# marlin_interface.net
KiCad netlist of a schematic drawn in EAGLE
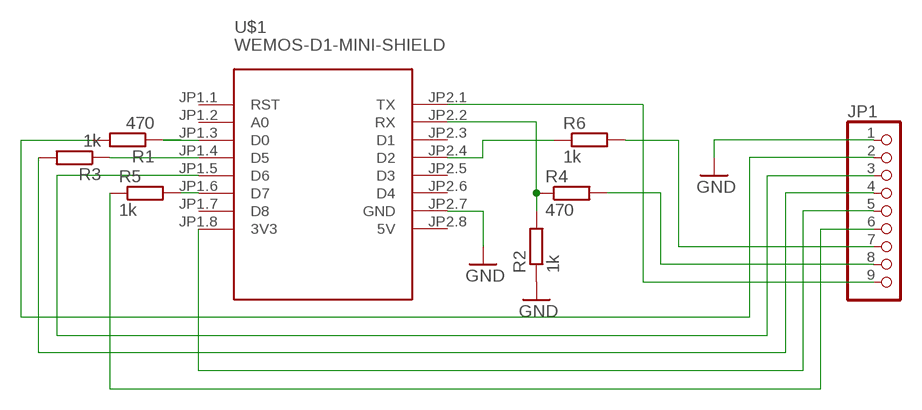
[diagram p0: schematic, sheet 1]

(export (version "E")
  (design (tool "Eeschema 10.0.6"))
  (components
    (comp (ref "JP1")
      (value "PINHD-1X9/90")
      (footprint "eagle-import:1X09_90")
      (libsource (lib "eagle-import") (part "PINHD-1X9/90"))
    )
    (comp (ref "R1")
      (value "470")
      (footprint "eagle-import:0204_5")
      (libsource (lib "eagle-import") (part "R-EU_0204/5"))
    )
    (comp (ref "R2")
      (value "1k")
      (footprint "eagle-import:0204_5")
      (libsource (lib "eagle-import") (part "R-EU_0204/5"))
    )
    (comp (ref "R3")
      (value "1k")
      (footprint "eagle-import:0204_5")
      (libsource (lib "eagle-import") (part "R-EU_0204/5"))
    )
    (comp (ref "R4")
      (value "470")
      (footprint "eagle-import:0204_5")
      (libsource (lib "eagle-import") (part "R-EU_0204/5"))
    )
    (comp (ref "R5")
      (value "1k")
      (footprint "eagle-import:0204_5")
      (libsource (lib "eagle-import") (part "R-EU_0204/5"))
    )
    (comp (ref "R6")
      (value "1k")
      (footprint "eagle-import:0204_5")
      (libsource (lib "eagle-import") (part "R-EU_0204/5"))
    )
    (comp (ref "U$1")
      (value "WEMOS-D1-MINI-SHIELD")
      (footprint "eagle-import:WEMOS-D1-MINI-SHIELD")
      (libsource (lib "eagle-import") (part "WEMOS-D1-MINI-SHIELD"))
    )
  )
  (nets
    (net (code "1") (name "/5V") (class "Default")
      (node (ref "U$1") (pin "JP2.8") (pinfunction "5V_JP2.8") (pintype "power_in"))
    )
    (net (code "2") (name "GND") (class "Default")
      (node (ref "JP1") (pin "1") (pinfunction "1_1") (pintype "passive"))
      (node (ref "R2") (pin "1") (pinfunction "1_1") (pintype "passive"))
      (node (ref "U$1") (pin "JP2.7") (pinfunction "GND_JP2.7") (pintype "power_in"))
    )
    (net (code "3") (name "Net-(JP1-Pad2)") (class "Default")
      (node (ref "JP1") (pin "2") (pinfunction "2_2") (pintype "passive"))
      (node (ref "R1") (pin "2") (pinfunction "2_2") (pintype "passive"))
    )
    (net (code "4") (name "Net-(JP1-Pad4)") (class "Default")
      (node (ref "JP1") (pin "4") (pinfunction "4_4") (pintype "passive"))
      (node (ref "R3") (pin "2") (pinfunction "2_2") (pintype "passive"))
    )
    (net (code "5") (name "Net-(JP1-Pad6)") (class "Default")
      (node (ref "JP1") (pin "6") (pinfunction "6_6") (pintype "passive"))
      (node (ref "R5") (pin "1") (pinfunction "1_1") (pintype "passive"))
    )
    (net (code "6") (name "Net-(JP1-Pad7)") (class "Default")
      (node (ref "JP1") (pin "7") (pinfunction "7_7") (pintype "passive"))
      (node (ref "R6") (pin "2") (pinfunction "2_2") (pintype "passive"))
    )
    (net (code "7") (name "Net-(JP1-Pad8)") (class "Default")
      (node (ref "JP1") (pin "8") (pinfunction "8_8") (pintype "passive"))
      (node (ref "R4") (pin "2") (pinfunction "2_2") (pintype "passive"))
    )
    (net (code "8") (name "Net-(U$1-3V3)") (class "Default")
      (node (ref "JP1") (pin "5") (pinfunction "5_5") (pintype "passive"))
      (node (ref "U$1") (pin "JP1.8") (pinfunction "3V3_JP1.8") (pintype "power_in"))
    )
    (net (code "9") (name "Net-(U$1-D0)") (class "Default")
      (node (ref "R1") (pin "1") (pinfunction "1_1") (pintype "passive"))
      (node (ref "U$1") (pin "JP1.3") (pinfunction "D0_JP1.3") (pintype "bidirectional"))
    )
    (net (code "10") (name "Net-(U$1-D2)") (class "Default")
      (node (ref "R6") (pin "1") (pinfunction "1_1") (pintype "passive"))
      (node (ref "U$1") (pin "JP2.4") (pinfunction "D2_JP2.4") (pintype "bidirectional"))
    )
    (net (code "11") (name "Net-(U$1-D5)") (class "Default")
      (node (ref "R3") (pin "1") (pinfunction "1_1") (pintype "passive"))
      (node (ref "U$1") (pin "JP1.4") (pinfunction "D5_JP1.4") (pintype "bidirectional"))
    )
    (net (code "12") (name "Net-(U$1-D6)") (class "Default")
      (node (ref "JP1") (pin "3") (pinfunction "3_3") (pintype "passive"))
      (node (ref "U$1") (pin "JP1.5") (pinfunction "D6_JP1.5") (pintype "bidirectional"))
    )
    (net (code "13") (name "Net-(U$1-D7)") (class "Default")
      (node (ref "R5") (pin "2") (pinfunction "2_2") (pintype "passive"))
      (node (ref "U$1") (pin "JP1.6") (pinfunction "D7_JP1.6") (pintype "bidirectional"))
    )
    (net (code "14") (name "Net-(U$1-RX)") (class "Default")
      (node (ref "R2") (pin "2") (pinfunction "2_2") (pintype "passive"))
      (node (ref "R4") (pin "1") (pinfunction "1_1") (pintype "passive"))
      (node (ref "U$1") (pin "JP2.2") (pinfunction "RX_JP2.2") (pintype "bidirectional"))
    )
    (net (code "15") (name "Net-(U$1-TX)") (class "Default")
      (node (ref "JP1") (pin "9") (pinfunction "9_9") (pintype "passive"))
      (node (ref "U$1") (pin "JP2.1") (pinfunction "TX_JP2.1") (pintype "bidirectional"))
    )
    (net (code "16") (name "unconnected-(U$1-A0-PadJP1.2)") (class "Default")
      (node (ref "U$1") (pin "JP1.2") (pinfunction "A0_JP1.2") (pintype "bidirectional"))
    )
    (net (code "17") (name "unconnected-(U$1-D1-PadJP2.3)") (class "Default")
      (node (ref "U$1") (pin "JP2.3") (pinfunction "D1_JP2.3") (pintype "bidirectional"))
    )
    (net (code "18") (name "unconnected-(U$1-D3-PadJP2.5)") (class "Default")
      (node (ref "U$1") (pin "JP2.5") (pinfunction "D3_JP2.5") (pintype "bidirectional"))
    )
    (net (code "19") (name "unconnected-(U$1-D4-PadJP2.6)") (class "Default")
      (node (ref "U$1") (pin "JP2.6") (pinfunction "D4_JP2.6") (pintype "bidirectional"))
    )
    (net (code "20") (name "unconnected-(U$1-D8-PadJP1.7)") (class "Default")
      (node (ref "U$1") (pin "JP1.7") (pinfunction "D8_JP1.7") (pintype "bidirectional"))
    )
    (net (code "21") (name "unconnected-(U$1-RST-PadJP1.1)") (class "Default")
      (node (ref "U$1") (pin "JP1.1") (pinfunction "RST_JP1.1") (pintype "bidirectional"))
    )
  )
)
